# osu-kb.net
KiCad netlist of a schematic drawn in EAGLE
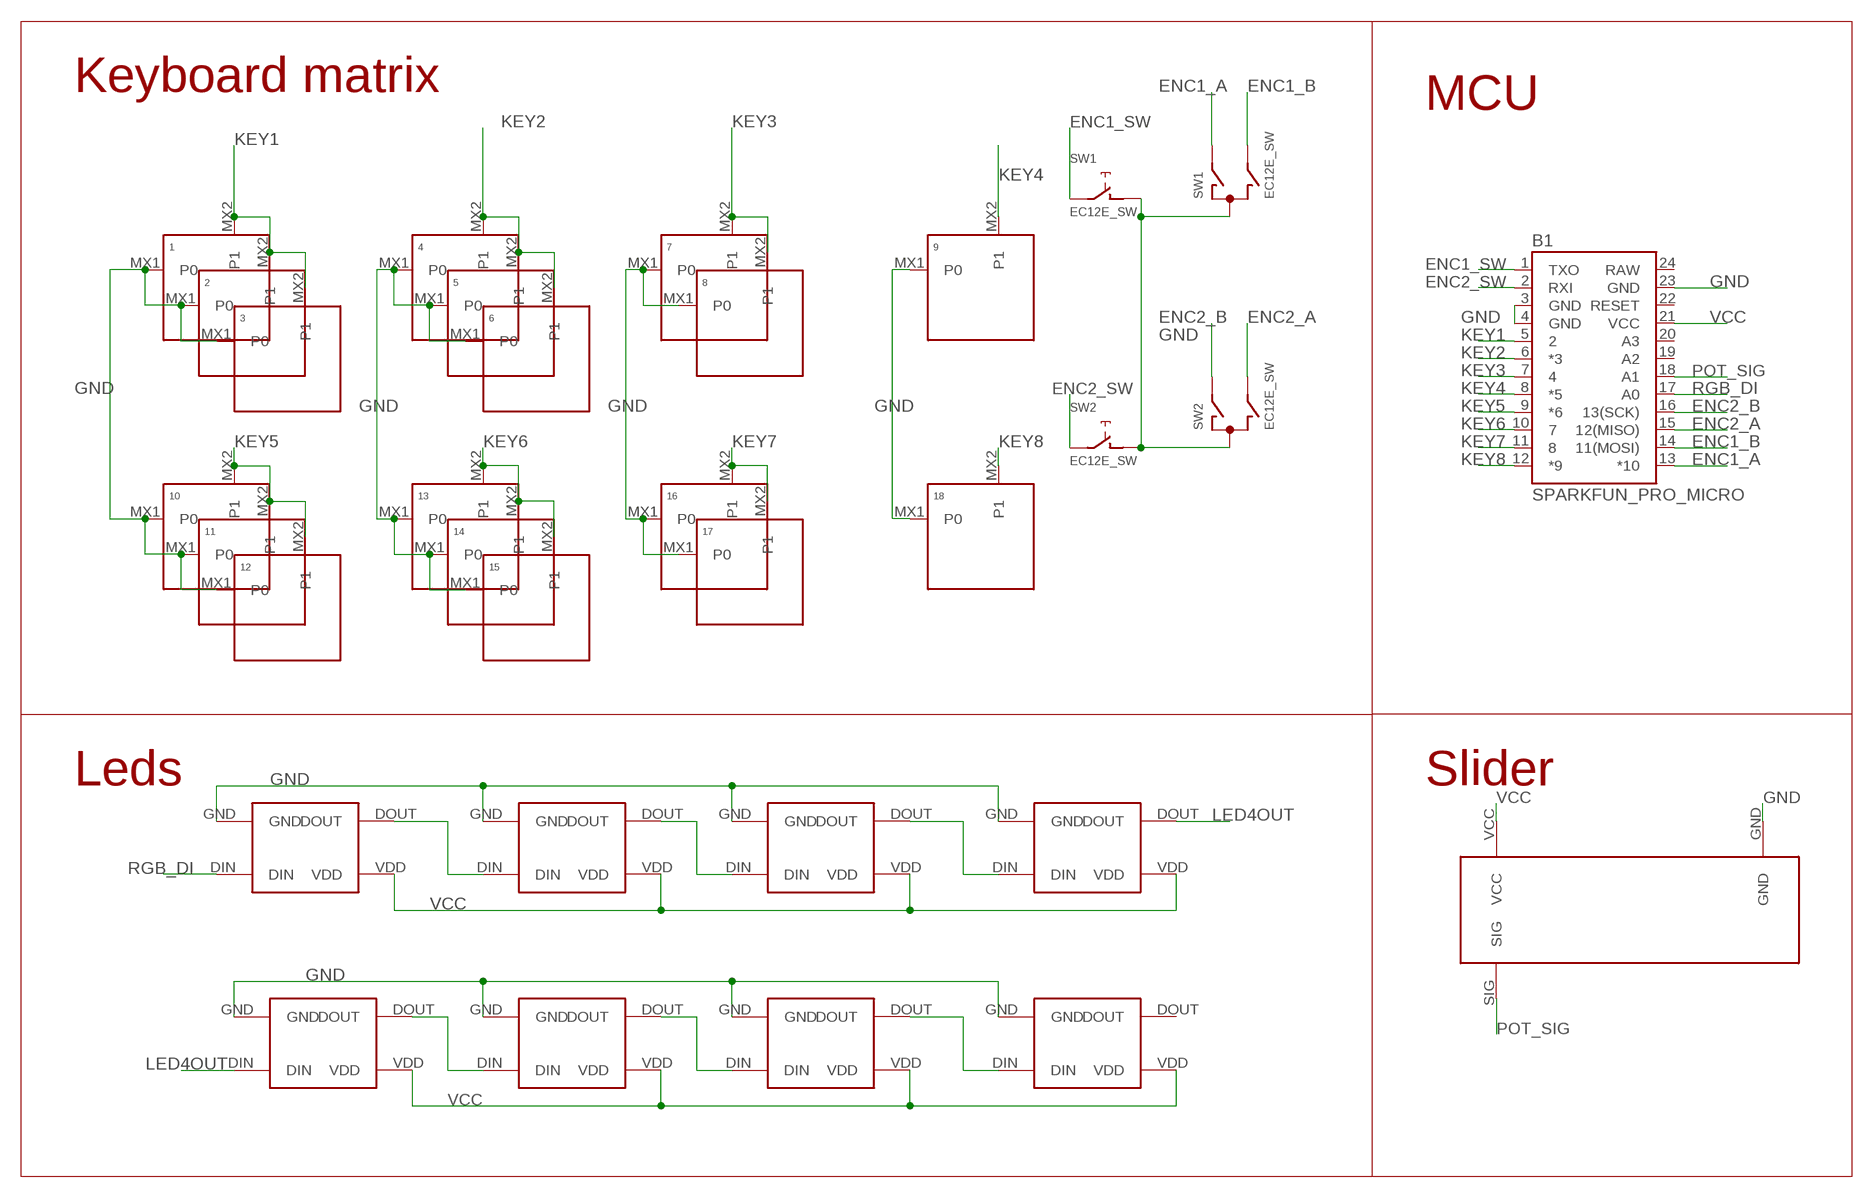
[diagram p0: schematic, sheet 1]

(export (version "E")
  (design (tool "Eeschema 10.0.6"))
  (components
    (comp (ref "1")
      (value "KEYSWITCH-PLAIN-MX-1U")
      (footprint "eagle-import:MX-1U")
      (libsource (lib "eagle-import") (part "KEYSWITCH-PLAIN-MX-1U"))
    )
    (comp (ref "2")
      (value "KEYSWITCH-PLAIN-MX-1U")
      (footprint "eagle-import:MX-1U")
      (libsource (lib "eagle-import") (part "KEYSWITCH-PLAIN-MX-1U"))
    )
    (comp (ref "3")
      (value "KEYSWITCH-PLAIN-MX-1U")
      (footprint "eagle-import:MX-1U")
      (libsource (lib "eagle-import") (part "KEYSWITCH-PLAIN-MX-1U"))
    )
    (comp (ref "4")
      (value "KEYSWITCH-PLAIN-MX-1U")
      (footprint "eagle-import:MX-1U")
      (libsource (lib "eagle-import") (part "KEYSWITCH-PLAIN-MX-1U"))
    )
    (comp (ref "5")
      (value "KEYSWITCH-PLAIN-MX-1U")
      (footprint "eagle-import:MX-1U")
      (libsource (lib "eagle-import") (part "KEYSWITCH-PLAIN-MX-1U"))
    )
    (comp (ref "6")
      (value "KEYSWITCH-PLAIN-MX-1U")
      (footprint "eagle-import:MX-1U")
      (libsource (lib "eagle-import") (part "KEYSWITCH-PLAIN-MX-1U"))
    )
    (comp (ref "7")
      (value "KEYSWITCH-PLAIN-MX-1U")
      (footprint "eagle-import:MX-1U")
      (libsource (lib "eagle-import") (part "KEYSWITCH-PLAIN-MX-1U"))
    )
    (comp (ref "8")
      (value "KEYSWITCH-PLAIN-MX-1U")
      (footprint "eagle-import:MX-1U")
      (libsource (lib "eagle-import") (part "KEYSWITCH-PLAIN-MX-1U"))
    )
    (comp (ref "9")
      (value "KEYSWITCH-PLAIN-MX-1U")
      (footprint "eagle-import:MX-1U")
      (libsource (lib "eagle-import") (part "KEYSWITCH-PLAIN-MX-1U"))
    )
    (comp (ref "10")
      (value "KEYSWITCH-PLAIN-MX-1U")
      (footprint "eagle-import:MX-1U")
      (libsource (lib "eagle-import") (part "KEYSWITCH-PLAIN-MX-1U"))
    )
    (comp (ref "11")
      (value "KEYSWITCH-PLAIN-MX-1U")
      (footprint "eagle-import:MX-1U")
      (libsource (lib "eagle-import") (part "KEYSWITCH-PLAIN-MX-1U"))
    )
    (comp (ref "12")
      (value "KEYSWITCH-PLAIN-MX-1U")
      (footprint "eagle-import:MX-1U")
      (libsource (lib "eagle-import") (part "KEYSWITCH-PLAIN-MX-1U"))
    )
    (comp (ref "13")
      (value "KEYSWITCH-PLAIN-MX-1U")
      (footprint "eagle-import:MX-1U")
      (libsource (lib "eagle-import") (part "KEYSWITCH-PLAIN-MX-1U"))
    )
    (comp (ref "14")
      (value "KEYSWITCH-PLAIN-MX-1U")
      (footprint "eagle-import:MX-1U")
      (libsource (lib "eagle-import") (part "KEYSWITCH-PLAIN-MX-1U"))
    )
    (comp (ref "15")
      (value "KEYSWITCH-PLAIN-MX-1U")
      (footprint "eagle-import:MX-1U")
      (libsource (lib "eagle-import") (part "KEYSWITCH-PLAIN-MX-1U"))
    )
    (comp (ref "16")
      (value "KEYSWITCH-PLAIN-MX-1U")
      (footprint "eagle-import:MX-1U")
      (libsource (lib "eagle-import") (part "KEYSWITCH-PLAIN-MX-1U"))
    )
    (comp (ref "17")
      (value "KEYSWITCH-PLAIN-MX-1U")
      (footprint "eagle-import:MX-1U")
      (libsource (lib "eagle-import") (part "KEYSWITCH-PLAIN-MX-1U"))
    )
    (comp (ref "18")
      (value "KEYSWITCH-PLAIN-MX-1U")
      (footprint "eagle-import:MX-1U")
      (libsource (lib "eagle-import") (part "KEYSWITCH-PLAIN-MX-1U"))
    )
    (comp (ref "B1")
      (value "SPARKFUN_PRO_MICRO")
      (footprint "eagle-import:SPARKFUN_PRO_MICRO")
      (libsource (lib "eagle-import") (part "SPARKFUN_PRO_MICRO"))
    )
    (comp (ref "SW1")
      (value "EC12E_SW")
      (footprint "eagle-import:ALPS_EC12E_SW")
      (fields (field (name "MPN") "EC12E2424407"))
      (libsource (lib "eagle-import") (part "EC12E_SW"))
    )
    (comp (ref "SW2")
      (value "EC12E_SW")
      (footprint "eagle-import:ALPS_EC12E_SW")
      (fields (field (name "MPN") "EC12E2424407"))
      (libsource (lib "eagle-import") (part "EC12E_SW"))
    )
    (comp (ref "U$1")
      (value "SK6812MINI-E")
      (footprint "eagle-import:SK6812MINI-E")
      (libsource (lib "eagle-import") (part "SK6812MINI-E"))
    )
    (comp (ref "U$2")
      (value "SK6812MINI-E")
      (footprint "eagle-import:SK6812MINI-E")
      (libsource (lib "eagle-import") (part "SK6812MINI-E"))
    )
    (comp (ref "U$3")
      (value "SK6812MINI-E")
      (footprint "eagle-import:SK6812MINI-E")
      (libsource (lib "eagle-import") (part "SK6812MINI-E"))
    )
    (comp (ref "U$4")
      (value "SK6812MINI-E")
      (footprint "eagle-import:SK6812MINI-E")
      (libsource (lib "eagle-import") (part "SK6812MINI-E"))
    )
    (comp (ref "U$5")
      (value "SK6812MINI-E")
      (footprint "eagle-import:SK6812MINI-E")
      (libsource (lib "eagle-import") (part "SK6812MINI-E"))
    )
    (comp (ref "U$6")
      (value "SK6812MINI-E")
      (footprint "eagle-import:SK6812MINI-E")
      (libsource (lib "eagle-import") (part "SK6812MINI-E"))
    )
    (comp (ref "U$7")
      (value "SK6812MINI-E")
      (footprint "eagle-import:SK6812MINI-E")
      (libsource (lib "eagle-import") (part "SK6812MINI-E"))
    )
    (comp (ref "U$8")
      (value "SK6812MINI-E")
      (footprint "eagle-import:SK6812MINI-E")
      (libsource (lib "eagle-import") (part "SK6812MINI-E"))
    )
    (comp (ref "U$9")
      (value "SH_SL60V_B10K")
      (footprint "eagle-import:SH_SL60V_B10K")
      (libsource (lib "eagle-import") (part "SH_SL60V_B10K"))
    )
  )
  (nets
    (net (code "1") (name "/ENC1_A") (class "Default")
      (node (ref "B1") (pin "13") (pinfunction "*10_13") (pintype "bidirectional"))
      (node (ref "SW1") (pin "A") (pinfunction "A_A") (pintype "passive"))
    )
    (net (code "2") (name "/ENC1_B") (class "Default")
      (node (ref "B1") (pin "14") (pinfunction "11(MOSI)_14") (pintype "bidirectional"))
      (node (ref "SW1") (pin "B") (pinfunction "B_B") (pintype "passive"))
    )
    (net (code "3") (name "/ENC1_SW") (class "Default")
      (node (ref "B1") (pin "1") (pinfunction "TXO_1") (pintype "bidirectional"))
      (node (ref "SW1") (pin "E") (pinfunction "2_E") (pintype "passive"))
    )
    (net (code "4") (name "/ENC2_A") (class "Default")
      (node (ref "B1") (pin "15") (pinfunction "12(MISO)_15") (pintype "bidirectional"))
      (node (ref "SW2") (pin "B") (pinfunction "B_B") (pintype "passive"))
    )
    (net (code "5") (name "/ENC2_B") (class "Default")
      (node (ref "B1") (pin "16") (pinfunction "13(SCK)_16") (pintype "bidirectional"))
      (node (ref "SW2") (pin "A") (pinfunction "A_A") (pintype "passive"))
    )
    (net (code "6") (name "/ENC2_SW") (class "Default")
      (node (ref "B1") (pin "2") (pinfunction "RXI_2") (pintype "bidirectional"))
      (node (ref "SW2") (pin "E") (pinfunction "2_E") (pintype "passive"))
    )
    (net (code "7") (name "/GND") (class "Default")
      (node (ref "1") (pin "MX1") (pinfunction "P0_MX1") (pintype "bidirectional"))
      (node (ref "10") (pin "MX1") (pinfunction "P0_MX1") (pintype "bidirectional"))
      (node (ref "11") (pin "MX1") (pinfunction "P0_MX1") (pintype "bidirectional"))
      (node (ref "12") (pin "MX1") (pinfunction "P0_MX1") (pintype "bidirectional"))
      (node (ref "13") (pin "MX1") (pinfunction "P0_MX1") (pintype "bidirectional"))
      (node (ref "14") (pin "MX1") (pinfunction "P0_MX1") (pintype "bidirectional"))
      (node (ref "15") (pin "MX1") (pinfunction "P0_MX1") (pintype "bidirectional"))
      (node (ref "16") (pin "MX1") (pinfunction "P0_MX1") (pintype "bidirectional"))
      (node (ref "17") (pin "MX1") (pinfunction "P0_MX1") (pintype "bidirectional"))
      (node (ref "18") (pin "MX1") (pinfunction "P0_MX1") (pintype "bidirectional"))
      (node (ref "2") (pin "MX1") (pinfunction "P0_MX1") (pintype "bidirectional"))
      (node (ref "3") (pin "MX1") (pinfunction "P0_MX1") (pintype "bidirectional"))
      (node (ref "4") (pin "MX1") (pinfunction "P0_MX1") (pintype "bidirectional"))
      (node (ref "5") (pin "MX1") (pinfunction "P0_MX1") (pintype "bidirectional"))
      (node (ref "6") (pin "MX1") (pinfunction "P0_MX1") (pintype "bidirectional"))
      (node (ref "7") (pin "MX1") (pinfunction "P0_MX1") (pintype "bidirectional"))
      (node (ref "8") (pin "MX1") (pinfunction "P0_MX1") (pintype "bidirectional"))
      (node (ref "9") (pin "MX1") (pinfunction "P0_MX1") (pintype "bidirectional"))
      (node (ref "B1") (pin "23") (pinfunction "GND_23") (pintype "power_in"))
      (node (ref "B1") (pin "3") (pinfunction "GND_3") (pintype "power_in"))
      (node (ref "B1") (pin "4") (pinfunction "GND_4") (pintype "power_in"))
      (node (ref "SW1") (pin "C") (pinfunction "C_C") (pintype "passive"))
      (node (ref "SW1") (pin "D") (pinfunction "1_D") (pintype "passive"))
      (node (ref "SW2") (pin "C") (pinfunction "C_C") (pintype "passive"))
      (node (ref "SW2") (pin "D") (pinfunction "1_D") (pintype "passive"))
      (node (ref "U$1") (pin "GND") (pinfunction "GND_GND") (pintype "bidirectional"))
      (node (ref "U$2") (pin "GND") (pinfunction "GND_GND") (pintype "bidirectional"))
      (node (ref "U$3") (pin "GND") (pinfunction "GND_GND") (pintype "bidirectional"))
      (node (ref "U$4") (pin "GND") (pinfunction "GND_GND") (pintype "bidirectional"))
      (node (ref "U$5") (pin "GND") (pinfunction "GND_GND") (pintype "bidirectional"))
      (node (ref "U$6") (pin "GND") (pinfunction "GND_GND") (pintype "bidirectional"))
      (node (ref "U$7") (pin "GND") (pinfunction "GND_GND") (pintype "bidirectional"))
      (node (ref "U$8") (pin "GND") (pinfunction "GND_GND") (pintype "bidirectional"))
      (node (ref "U$9") (pin "GND") (pinfunction "GND_GND") (pintype "bidirectional"))
    )
    (net (code "8") (name "/KEY1") (class "Default")
      (node (ref "1") (pin "MX2") (pinfunction "P1_MX2") (pintype "bidirectional"))
      (node (ref "2") (pin "MX2") (pinfunction "P1_MX2") (pintype "bidirectional"))
      (node (ref "3") (pin "MX2") (pinfunction "P1_MX2") (pintype "bidirectional"))
      (node (ref "B1") (pin "5") (pinfunction "2_5") (pintype "bidirectional"))
    )
    (net (code "9") (name "/KEY2") (class "Default")
      (node (ref "4") (pin "MX2") (pinfunction "P1_MX2") (pintype "bidirectional"))
      (node (ref "5") (pin "MX2") (pinfunction "P1_MX2") (pintype "bidirectional"))
      (node (ref "6") (pin "MX2") (pinfunction "P1_MX2") (pintype "bidirectional"))
      (node (ref "B1") (pin "6") (pinfunction "*3_6") (pintype "bidirectional"))
    )
    (net (code "10") (name "/KEY3") (class "Default")
      (node (ref "7") (pin "MX2") (pinfunction "P1_MX2") (pintype "bidirectional"))
      (node (ref "8") (pin "MX2") (pinfunction "P1_MX2") (pintype "bidirectional"))
      (node (ref "B1") (pin "7") (pinfunction "4_7") (pintype "bidirectional"))
    )
    (net (code "11") (name "/KEY4") (class "Default")
      (node (ref "9") (pin "MX2") (pinfunction "P1_MX2") (pintype "bidirectional"))
      (node (ref "B1") (pin "8") (pinfunction "*5_8") (pintype "bidirectional"))
    )
    (net (code "12") (name "/KEY5") (class "Default")
      (node (ref "10") (pin "MX2") (pinfunction "P1_MX2") (pintype "bidirectional"))
      (node (ref "11") (pin "MX2") (pinfunction "P1_MX2") (pintype "bidirectional"))
      (node (ref "12") (pin "MX2") (pinfunction "P1_MX2") (pintype "bidirectional"))
      (node (ref "B1") (pin "9") (pinfunction "*6_9") (pintype "bidirectional"))
    )
    (net (code "13") (name "/KEY6") (class "Default")
      (node (ref "13") (pin "MX2") (pinfunction "P1_MX2") (pintype "bidirectional"))
      (node (ref "14") (pin "MX2") (pinfunction "P1_MX2") (pintype "bidirectional"))
      (node (ref "15") (pin "MX2") (pinfunction "P1_MX2") (pintype "bidirectional"))
      (node (ref "B1") (pin "10") (pinfunction "7_10") (pintype "bidirectional"))
    )
    (net (code "14") (name "/KEY7") (class "Default")
      (node (ref "16") (pin "MX2") (pinfunction "P1_MX2") (pintype "bidirectional"))
      (node (ref "17") (pin "MX2") (pinfunction "P1_MX2") (pintype "bidirectional"))
      (node (ref "B1") (pin "11") (pinfunction "8_11") (pintype "bidirectional"))
    )
    (net (code "15") (name "/KEY8") (class "Default")
      (node (ref "18") (pin "MX2") (pinfunction "P1_MX2") (pintype "bidirectional"))
      (node (ref "B1") (pin "12") (pinfunction "*9_12") (pintype "bidirectional"))
    )
    (net (code "16") (name "/LED4OUT") (class "Default")
      (node (ref "U$4") (pin "DOUT") (pinfunction "DOUT_DOUT") (pintype "bidirectional"))
      (node (ref "U$5") (pin "DIN") (pinfunction "DIN_DIN") (pintype "bidirectional"))
    )
    (net (code "17") (name "/POT_SIG") (class "Default")
      (node (ref "B1") (pin "18") (pinfunction "A1_18") (pintype "bidirectional"))
      (node (ref "U$9") (pin "SIG") (pinfunction "SIG_SIG") (pintype "bidirectional"))
    )
    (net (code "18") (name "/RAW") (class "Default")
      (node (ref "B1") (pin "24") (pinfunction "RAW_24") (pintype "power_in"))
    )
    (net (code "19") (name "/RGB_DI") (class "Default")
      (node (ref "B1") (pin "17") (pinfunction "A0_17") (pintype "bidirectional"))
      (node (ref "U$1") (pin "DIN") (pinfunction "DIN_DIN") (pintype "bidirectional"))
    )
    (net (code "20") (name "/VCC") (class "Default")
      (node (ref "B1") (pin "21") (pinfunction "VCC_21") (pintype "power_in"))
      (node (ref "U$1") (pin "VDD") (pinfunction "VDD_VDD") (pintype "bidirectional"))
      (node (ref "U$2") (pin "VDD") (pinfunction "VDD_VDD") (pintype "bidirectional"))
      (node (ref "U$3") (pin "VDD") (pinfunction "VDD_VDD") (pintype "bidirectional"))
      (node (ref "U$4") (pin "VDD") (pinfunction "VDD_VDD") (pintype "bidirectional"))
      (node (ref "U$5") (pin "VDD") (pinfunction "VDD_VDD") (pintype "bidirectional"))
      (node (ref "U$6") (pin "VDD") (pinfunction "VDD_VDD") (pintype "bidirectional"))
      (node (ref "U$7") (pin "VDD") (pinfunction "VDD_VDD") (pintype "bidirectional"))
      (node (ref "U$8") (pin "VDD") (pinfunction "VDD_VDD") (pintype "bidirectional"))
      (node (ref "U$9") (pin "VCC") (pinfunction "VCC_VCC") (pintype "bidirectional"))
    )
    (net (code "21") (name "Net-(U$1-PadDOUT)") (class "Default")
      (node (ref "U$1") (pin "DOUT") (pinfunction "DOUT_DOUT") (pintype "bidirectional"))
      (node (ref "U$2") (pin "DIN") (pinfunction "DIN_DIN") (pintype "bidirectional"))
    )
    (net (code "22") (name "Net-(U$2-PadDOUT)") (class "Default")
      (node (ref "U$2") (pin "DOUT") (pinfunction "DOUT_DOUT") (pintype "bidirectional"))
      (node (ref "U$3") (pin "DIN") (pinfunction "DIN_DIN") (pintype "bidirectional"))
    )
    (net (code "23") (name "Net-(U$3-PadDOUT)") (class "Default")
      (node (ref "U$3") (pin "DOUT") (pinfunction "DOUT_DOUT") (pintype "bidirectional"))
      (node (ref "U$4") (pin "DIN") (pinfunction "DIN_DIN") (pintype "bidirectional"))
    )
    (net (code "24") (name "Net-(U$5-PadDOUT)") (class "Default")
      (node (ref "U$5") (pin "DOUT") (pinfunction "DOUT_DOUT") (pintype "bidirectional"))
      (node (ref "U$6") (pin "DIN") (pinfunction "DIN_DIN") (pintype "bidirectional"))
    )
    (net (code "25") (name "Net-(U$6-PadDOUT)") (class "Default")
      (node (ref "U$6") (pin "DOUT") (pinfunction "DOUT_DOUT") (pintype "bidirectional"))
      (node (ref "U$7") (pin "DIN") (pinfunction "DIN_DIN") (pintype "bidirectional"))
    )
    (net (code "26") (name "Net-(U$7-PadDOUT)") (class "Default")
      (node (ref "U$7") (pin "DOUT") (pinfunction "DOUT_DOUT") (pintype "bidirectional"))
      (node (ref "U$8") (pin "DIN") (pinfunction "DIN_DIN") (pintype "bidirectional"))
    )
    (net (code "27") (name "unconnected-(B1-A2-Pad19)") (class "Default")
      (node (ref "B1") (pin "19") (pinfunction "A2_19") (pintype "bidirectional"))
    )
    (net (code "28") (name "unconnected-(B1-A3-Pad20)") (class "Default")
      (node (ref "B1") (pin "20") (pinfunction "A3_20") (pintype "bidirectional"))
    )
    (net (code "29") (name "unconnected-(B1-RESET-Pad22)") (class "Default")
      (node (ref "B1") (pin "22") (pinfunction "RESET_22") (pintype "bidirectional"))
    )
    (net (code "30") (name "unconnected-(U$8-PadDOUT)") (class "Default")
      (node (ref "U$8") (pin "DOUT") (pinfunction "DOUT_DOUT") (pintype "bidirectional"))
    )
  )
)
